# Memory.net
KiCad netlist of a schematic drawn in Altium Designer
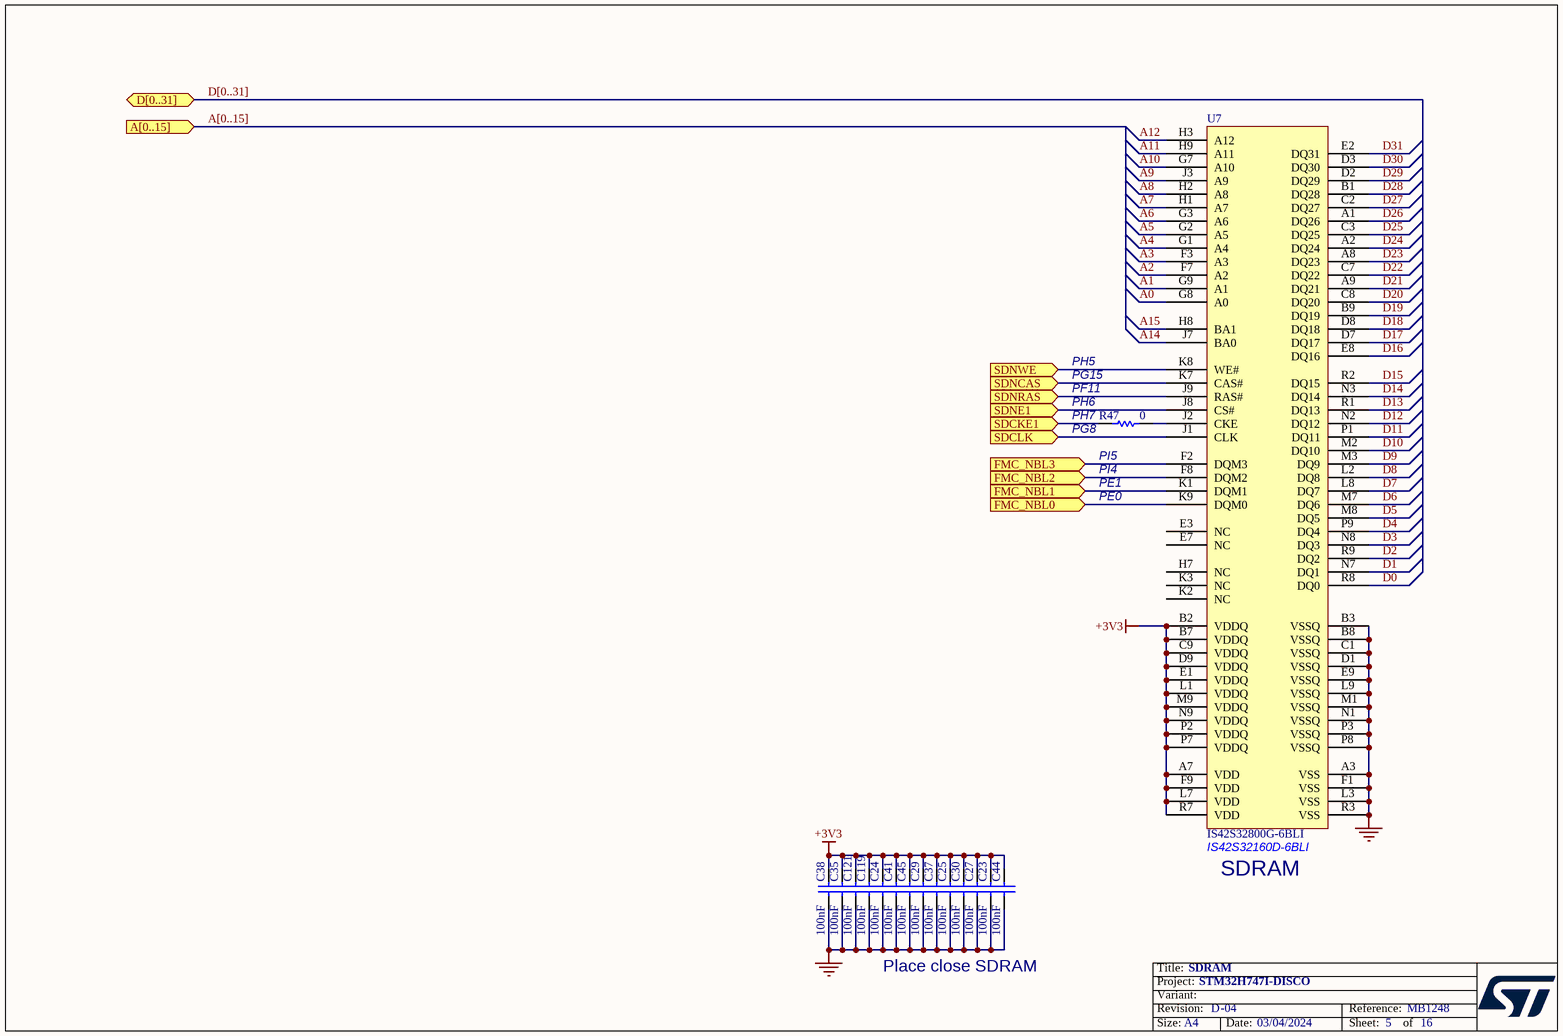
[diagram p0: Memory.SchDoc]

(export (version "E")
  (design (tool "Eeschema 10.0.6"))
  (components
    (comp (ref "C23")
      (value "100nF")
      (footprint "0603C")
      (description "Capacitor")
      (fields (field (name "PUBLISHER") "Altium Limited"))
      (libsource (lib "Miscellaneous Devices") (part "Cap"))
    )
    (comp (ref "C24")
      (value "100nF")
      (footprint "0603C")
      (description "Capacitor")
      (fields (field (name "PUBLISHER") "Altium Limited"))
      (libsource (lib "Miscellaneous Devices") (part "Cap"))
    )
    (comp (ref "C25")
      (value "100nF")
      (footprint "0603C")
      (description "Capacitor")
      (fields (field (name "PUBLISHER") "Altium Limited"))
      (libsource (lib "Miscellaneous Devices") (part "Cap"))
    )
    (comp (ref "C27")
      (value "100nF")
      (footprint "0603C")
      (description "Capacitor")
      (fields (field (name "PUBLISHER") "Altium Limited"))
      (libsource (lib "Miscellaneous Devices") (part "Cap"))
    )
    (comp (ref "C29")
      (value "100nF")
      (footprint "0603C")
      (description "Capacitor")
      (fields (field (name "PUBLISHER") "Altium Limited"))
      (libsource (lib "Miscellaneous Devices") (part "Cap"))
    )
    (comp (ref "C30")
      (value "100nF")
      (footprint "0603C")
      (description "Capacitor")
      (fields (field (name "PUBLISHER") "Altium Limited"))
      (libsource (lib "Miscellaneous Devices") (part "Cap"))
    )
    (comp (ref "C35")
      (value "100nF")
      (footprint "0603C")
      (description "Capacitor")
      (fields (field (name "PUBLISHER") "Altium Limited"))
      (libsource (lib "Miscellaneous Devices") (part "Cap"))
    )
    (comp (ref "C37")
      (value "100nF")
      (footprint "0603C")
      (description "Capacitor")
      (fields (field (name "PUBLISHER") "Altium Limited"))
      (libsource (lib "Miscellaneous Devices") (part "Cap"))
    )
    (comp (ref "C38")
      (value "100nF")
      (footprint "0603C")
      (description "Capacitor")
      (fields (field (name "PUBLISHER") "Altium Limited"))
      (libsource (lib "Miscellaneous Devices") (part "Cap"))
    )
    (comp (ref "C41")
      (value "100nF")
      (footprint "0603C")
      (description "Capacitor")
      (fields (field (name "PUBLISHER") "Altium Limited"))
      (libsource (lib "Miscellaneous Devices") (part "Cap"))
    )
    (comp (ref "C44")
      (value "100nF")
      (footprint "0603C")
      (description "Capacitor")
      (fields (field (name "PUBLISHER") "Altium Limited"))
      (libsource (lib "Miscellaneous Devices") (part "Cap"))
    )
    (comp (ref "C45")
      (value "100nF")
      (footprint "0603C")
      (description "Capacitor")
      (fields (field (name "PUBLISHER") "Altium Limited"))
      (libsource (lib "Miscellaneous Devices") (part "Cap"))
    )
    (comp (ref "C119")
      (value "100nF")
      (footprint "0603C")
      (description "Capacitor")
      (fields (field (name "PUBLISHER") "Altium Limited"))
      (libsource (lib "Miscellaneous Devices") (part "Cap"))
    )
    (comp (ref "C121")
      (value "100nF")
      (footprint "0603C")
      (description "Capacitor")
      (fields (field (name "PUBLISHER") "Altium Limited"))
      (libsource (lib "Miscellaneous Devices") (part "Cap"))
    )
    (comp (ref "R47")
      (value "0")
      (footprint "0603R")
      (description "Resistor")
      (fields (field (name "PUBLISHER") "Altium Limited"))
      (libsource (lib "Miscellaneous Devices") (part "Res1"))
    )
    (comp (ref "U7")
      (value "IS42S32800G-6BLI")
      (footprint "FBGA90_0R8_8X13")
      (libsource (lib "MB1248_1") (part "IS42S32160D-6BLI"))
    )
  )
  (nets
    (net (code "2") (name "+3V3") (class "Default")
      (node (ref "C119") (pin "1") (pinfunction "1_1") (pintype "passive"))
      (node (ref "C121") (pin "1") (pinfunction "1_1") (pintype "passive"))
      (node (ref "C23") (pin "1") (pinfunction "1_1") (pintype "passive"))
      (node (ref "C24") (pin "1") (pinfunction "1_1") (pintype "passive"))
      (node (ref "C25") (pin "1") (pinfunction "1_1") (pintype "passive"))
      (node (ref "C27") (pin "1") (pinfunction "1_1") (pintype "passive"))
      (node (ref "C29") (pin "1") (pinfunction "1_1") (pintype "passive"))
      (node (ref "C30") (pin "1") (pinfunction "1_1") (pintype "passive"))
      (node (ref "C35") (pin "1") (pinfunction "1_1") (pintype "passive"))
      (node (ref "C37") (pin "1") (pinfunction "1_1") (pintype "passive"))
      (node (ref "C38") (pin "1") (pinfunction "1_1") (pintype "passive"))
      (node (ref "C41") (pin "1") (pinfunction "1_1") (pintype "passive"))
      (node (ref "C44") (pin "1") (pinfunction "1_1") (pintype "passive"))
      (node (ref "C45") (pin "1") (pinfunction "1_1") (pintype "passive"))
      (node (ref "U7") (pin "A7") (pinfunction "VDD_A7") (pintype "passive"))
      (node (ref "U7") (pin "B2") (pinfunction "VDDQ_B2") (pintype "passive"))
      (node (ref "U7") (pin "B7") (pinfunction "VDDQ_B7") (pintype "passive"))
      (node (ref "U7") (pin "C9") (pinfunction "VDDQ_C9") (pintype "passive"))
      (node (ref "U7") (pin "D9") (pinfunction "VDDQ_D9") (pintype "passive"))
      (node (ref "U7") (pin "E1") (pinfunction "VDDQ_E1") (pintype "passive"))
      (node (ref "U7") (pin "F9") (pinfunction "VDD_F9") (pintype "passive"))
      (node (ref "U7") (pin "L1") (pinfunction "VDDQ_L1") (pintype "passive"))
      (node (ref "U7") (pin "L7") (pinfunction "VDD_L7") (pintype "passive"))
      (node (ref "U7") (pin "M9") (pinfunction "VDDQ_M9") (pintype "passive"))
      (node (ref "U7") (pin "N9") (pinfunction "VDDQ_N9") (pintype "passive"))
      (node (ref "U7") (pin "P2") (pinfunction "VDDQ_P2") (pintype "passive"))
      (node (ref "U7") (pin "P7") (pinfunction "VDDQ_P7") (pintype "passive"))
      (node (ref "U7") (pin "R7") (pinfunction "VDD_R7") (pintype "passive"))
    )
    (net (code "3") (name "/A0") (class "Default")
      (node (ref "U7") (pin "G8") (pinfunction "A0_G8") (pintype "passive"))
    )
    (net (code "4") (name "/A1") (class "Default")
      (node (ref "U7") (pin "G9") (pinfunction "A1_G9") (pintype "passive"))
    )
    (net (code "5") (name "/A2") (class "Default")
      (node (ref "U7") (pin "F7") (pinfunction "A2_F7") (pintype "passive"))
    )
    (net (code "6") (name "/A3") (class "Default")
      (node (ref "U7") (pin "F3") (pinfunction "A3_F3") (pintype "passive"))
    )
    (net (code "7") (name "/A4") (class "Default")
      (node (ref "U7") (pin "G1") (pinfunction "A4_G1") (pintype "passive"))
    )
    (net (code "8") (name "/A5") (class "Default")
      (node (ref "U7") (pin "G2") (pinfunction "A5_G2") (pintype "passive"))
    )
    (net (code "9") (name "/A6") (class "Default")
      (node (ref "U7") (pin "G3") (pinfunction "A6_G3") (pintype "passive"))
    )
    (net (code "10") (name "/A7") (class "Default")
      (node (ref "U7") (pin "H1") (pinfunction "A7_H1") (pintype "passive"))
    )
    (net (code "11") (name "/A8") (class "Default")
      (node (ref "U7") (pin "H2") (pinfunction "A8_H2") (pintype "passive"))
    )
    (net (code "12") (name "/A9") (class "Default")
      (node (ref "U7") (pin "J3") (pinfunction "A9_J3") (pintype "passive"))
    )
    (net (code "13") (name "/A10") (class "Default")
      (node (ref "U7") (pin "G7") (pinfunction "A10_G7") (pintype "passive"))
    )
    (net (code "14") (name "/A11") (class "Default")
      (node (ref "U7") (pin "H9") (pinfunction "A11_H9") (pintype "passive"))
    )
    (net (code "15") (name "/A12") (class "Default")
      (node (ref "U7") (pin "H3") (pinfunction "A12_H3") (pintype "passive"))
    )
    (net (code "16") (name "/A14") (class "Default")
      (node (ref "U7") (pin "J7") (pinfunction "BA0_J7") (pintype "passive"))
    )
    (net (code "17") (name "/A15") (class "Default")
      (node (ref "U7") (pin "H8") (pinfunction "BA1_H8") (pintype "passive"))
    )
    (net (code "19") (name "/D0") (class "Default")
      (node (ref "U7") (pin "R8") (pinfunction "DQ0_R8") (pintype "passive"))
    )
    (net (code "20") (name "/D1") (class "Default")
      (node (ref "U7") (pin "N7") (pinfunction "DQ1_N7") (pintype "passive"))
    )
    (net (code "21") (name "/D2") (class "Default")
      (node (ref "U7") (pin "R9") (pinfunction "DQ2_R9") (pintype "passive"))
    )
    (net (code "22") (name "/D3") (class "Default")
      (node (ref "U7") (pin "N8") (pinfunction "DQ3_N8") (pintype "passive"))
    )
    (net (code "23") (name "/D4") (class "Default")
      (node (ref "U7") (pin "P9") (pinfunction "DQ4_P9") (pintype "passive"))
    )
    (net (code "24") (name "/D5") (class "Default")
      (node (ref "U7") (pin "M8") (pinfunction "DQ5_M8") (pintype "passive"))
    )
    (net (code "25") (name "/D6") (class "Default")
      (node (ref "U7") (pin "M7") (pinfunction "DQ6_M7") (pintype "passive"))
    )
    (net (code "26") (name "/D7") (class "Default")
      (node (ref "U7") (pin "L8") (pinfunction "DQ7_L8") (pintype "passive"))
    )
    (net (code "27") (name "/D8") (class "Default")
      (node (ref "U7") (pin "L2") (pinfunction "DQ8_L2") (pintype "passive"))
    )
    (net (code "28") (name "/D9") (class "Default")
      (node (ref "U7") (pin "M3") (pinfunction "DQ9_M3") (pintype "passive"))
    )
    (net (code "29") (name "/D10") (class "Default")
      (node (ref "U7") (pin "M2") (pinfunction "DQ10_M2") (pintype "passive"))
    )
    (net (code "30") (name "/D11") (class "Default")
      (node (ref "U7") (pin "P1") (pinfunction "DQ11_P1") (pintype "passive"))
    )
    (net (code "31") (name "/D12") (class "Default")
      (node (ref "U7") (pin "N2") (pinfunction "DQ12_N2") (pintype "passive"))
    )
    (net (code "32") (name "/D13") (class "Default")
      (node (ref "U7") (pin "R1") (pinfunction "DQ13_R1") (pintype "passive"))
    )
    (net (code "33") (name "/D14") (class "Default")
      (node (ref "U7") (pin "N3") (pinfunction "DQ14_N3") (pintype "passive"))
    )
    (net (code "34") (name "/D15") (class "Default")
      (node (ref "U7") (pin "R2") (pinfunction "DQ15_R2") (pintype "passive"))
    )
    (net (code "35") (name "/D16") (class "Default")
      (node (ref "U7") (pin "E8") (pinfunction "DQ16_E8") (pintype "passive"))
    )
    (net (code "36") (name "/D17") (class "Default")
      (node (ref "U7") (pin "D7") (pinfunction "DQ17_D7") (pintype "passive"))
    )
    (net (code "37") (name "/D18") (class "Default")
      (node (ref "U7") (pin "D8") (pinfunction "DQ18_D8") (pintype "passive"))
    )
    (net (code "38") (name "/D19") (class "Default")
      (node (ref "U7") (pin "B9") (pinfunction "DQ19_B9") (pintype "passive"))
    )
    (net (code "39") (name "/D20") (class "Default")
      (node (ref "U7") (pin "C8") (pinfunction "DQ20_C8") (pintype "passive"))
    )
    (net (code "40") (name "/D21") (class "Default")
      (node (ref "U7") (pin "A9") (pinfunction "DQ21_A9") (pintype "passive"))
    )
    (net (code "41") (name "/D22") (class "Default")
      (node (ref "U7") (pin "C7") (pinfunction "DQ22_C7") (pintype "passive"))
    )
    (net (code "42") (name "/D23") (class "Default")
      (node (ref "U7") (pin "A8") (pinfunction "DQ23_A8") (pintype "passive"))
    )
    (net (code "43") (name "/D24") (class "Default")
      (node (ref "U7") (pin "A2") (pinfunction "DQ24_A2") (pintype "passive"))
    )
    (net (code "44") (name "/D25") (class "Default")
      (node (ref "U7") (pin "C3") (pinfunction "DQ25_C3") (pintype "passive"))
    )
    (net (code "45") (name "/D26") (class "Default")
      (node (ref "U7") (pin "A1") (pinfunction "DQ26_A1") (pintype "passive"))
    )
    (net (code "46") (name "/D27") (class "Default")
      (node (ref "U7") (pin "C2") (pinfunction "DQ27_C2") (pintype "passive"))
    )
    (net (code "47") (name "/D28") (class "Default")
      (node (ref "U7") (pin "B1") (pinfunction "DQ28_B1") (pintype "passive"))
    )
    (net (code "48") (name "/D29") (class "Default")
      (node (ref "U7") (pin "D2") (pinfunction "DQ29_D2") (pintype "passive"))
    )
    (net (code "49") (name "/D30") (class "Default")
      (node (ref "U7") (pin "D3") (pinfunction "DQ30_D3") (pintype "passive"))
    )
    (net (code "50") (name "/D31") (class "Default")
      (node (ref "U7") (pin "E2") (pinfunction "DQ31_E2") (pintype "passive"))
    )
    (net (code "52") (name "/FMC_NBL0") (class "Default")
      (node (ref "U7") (pin "K9") (pinfunction "DQM0_K9") (pintype "passive"))
    )
    (net (code "53") (name "/FMC_NBL1") (class "Default")
      (node (ref "U7") (pin "K1") (pinfunction "DQM1_K1") (pintype "passive"))
    )
    (net (code "54") (name "/FMC_NBL2") (class "Default")
      (node (ref "U7") (pin "F8") (pinfunction "DQM2_F8") (pintype "passive"))
    )
    (net (code "55") (name "/FMC_NBL3") (class "Default")
      (node (ref "U7") (pin "F2") (pinfunction "DQM3_F2") (pintype "passive"))
    )
    (net (code "56") (name "/SDCKE1") (class "Default")
      (node (ref "R47") (pin "2") (pinfunction "2_2") (pintype "passive"))
    )
    (net (code "57") (name "/SDCLK") (class "Default")
      (node (ref "U7") (pin "J1") (pinfunction "CLK_J1") (pintype "passive"))
    )
    (net (code "58") (name "/SDNCAS") (class "Default")
      (node (ref "U7") (pin "K7") (pinfunction "CAS#_K7") (pintype "passive"))
    )
    (net (code "59") (name "/SDNE1") (class "Default")
      (node (ref "U7") (pin "J8") (pinfunction "CS#_J8") (pintype "passive"))
    )
    (net (code "60") (name "/SDNRAS") (class "Default")
      (node (ref "U7") (pin "J9") (pinfunction "RAS#_J9") (pintype "passive"))
    )
    (net (code "61") (name "/SDNWE") (class "Default")
      (node (ref "U7") (pin "K8") (pinfunction "WE#_K8") (pintype "passive"))
    )
    (net (code "62") (name "GND") (class "Default")
      (node (ref "C119") (pin "2") (pinfunction "2_2") (pintype "passive"))
      (node (ref "C121") (pin "2") (pinfunction "2_2") (pintype "passive"))
      (node (ref "C23") (pin "2") (pinfunction "2_2") (pintype "passive"))
      (node (ref "C24") (pin "2") (pinfunction "2_2") (pintype "passive"))
      (node (ref "C25") (pin "2") (pinfunction "2_2") (pintype "passive"))
      (node (ref "C27") (pin "2") (pinfunction "2_2") (pintype "passive"))
      (node (ref "C29") (pin "2") (pinfunction "2_2") (pintype "passive"))
      (node (ref "C30") (pin "2") (pinfunction "2_2") (pintype "passive"))
      (node (ref "C35") (pin "2") (pinfunction "2_2") (pintype "passive"))
      (node (ref "C37") (pin "2") (pinfunction "2_2") (pintype "passive"))
      (node (ref "C38") (pin "2") (pinfunction "2_2") (pintype "passive"))
      (node (ref "C41") (pin "2") (pinfunction "2_2") (pintype "passive"))
      (node (ref "C44") (pin "2") (pinfunction "2_2") (pintype "passive"))
      (node (ref "C45") (pin "2") (pinfunction "2_2") (pintype "passive"))
      (node (ref "U7") (pin "A3") (pinfunction "VSS_A3") (pintype "passive"))
      (node (ref "U7") (pin "B3") (pinfunction "VSSQ_B3") (pintype "passive"))
      (node (ref "U7") (pin "B8") (pinfunction "VSSQ_B8") (pintype "passive"))
      (node (ref "U7") (pin "C1") (pinfunction "VSSQ_C1") (pintype "passive"))
      (node (ref "U7") (pin "D1") (pinfunction "VSSQ_D1") (pintype "passive"))
      (node (ref "U7") (pin "E9") (pinfunction "VSSQ_E9") (pintype "passive"))
      (node (ref "U7") (pin "F1") (pinfunction "VSS_F1") (pintype "passive"))
      (node (ref "U7") (pin "L3") (pinfunction "VSS_L3") (pintype "passive"))
      (node (ref "U7") (pin "L9") (pinfunction "VSSQ_L9") (pintype "passive"))
      (node (ref "U7") (pin "M1") (pinfunction "VSSQ_M1") (pintype "passive"))
      (node (ref "U7") (pin "N1") (pinfunction "VSSQ_N1") (pintype "passive"))
      (node (ref "U7") (pin "P3") (pinfunction "VSSQ_P3") (pintype "passive"))
      (node (ref "U7") (pin "P8") (pinfunction "VSSQ_P8") (pintype "passive"))
      (node (ref "U7") (pin "R3") (pinfunction "VSS_R3") (pintype "passive"))
    )
    (net (code "63") (name "Net-(U7-CKE)") (class "Default")
      (node (ref "R47") (pin "1") (pinfunction "1_1") (pintype "passive"))
      (node (ref "U7") (pin "J2") (pinfunction "CKE_J2") (pintype "passive"))
    )
    (net (code "64") (name "unconnected-(U7-NC-PadE3)") (class "Default")
      (node (ref "U7") (pin "E3") (pinfunction "NC_E3") (pintype "passive"))
    )
    (net (code "65") (name "unconnected-(U7-NC-PadE7)") (class "Default")
      (node (ref "U7") (pin "E7") (pinfunction "NC_E7") (pintype "passive"))
    )
    (net (code "66") (name "unconnected-(U7-NC-PadH7)") (class "Default")
      (node (ref "U7") (pin "H7") (pinfunction "NC_H7") (pintype "passive"))
    )
    (net (code "67") (name "unconnected-(U7-NC-PadK2)") (class "Default")
      (node (ref "U7") (pin "K2") (pinfunction "NC_K2") (pintype "passive"))
    )
    (net (code "68") (name "unconnected-(U7-NC-PadK3)") (class "Default")
      (node (ref "U7") (pin "K3") (pinfunction "NC_K3") (pintype "passive"))
    )
  )
)
